# MCU.net
KiCad netlist of a schematic drawn in Altium Designer
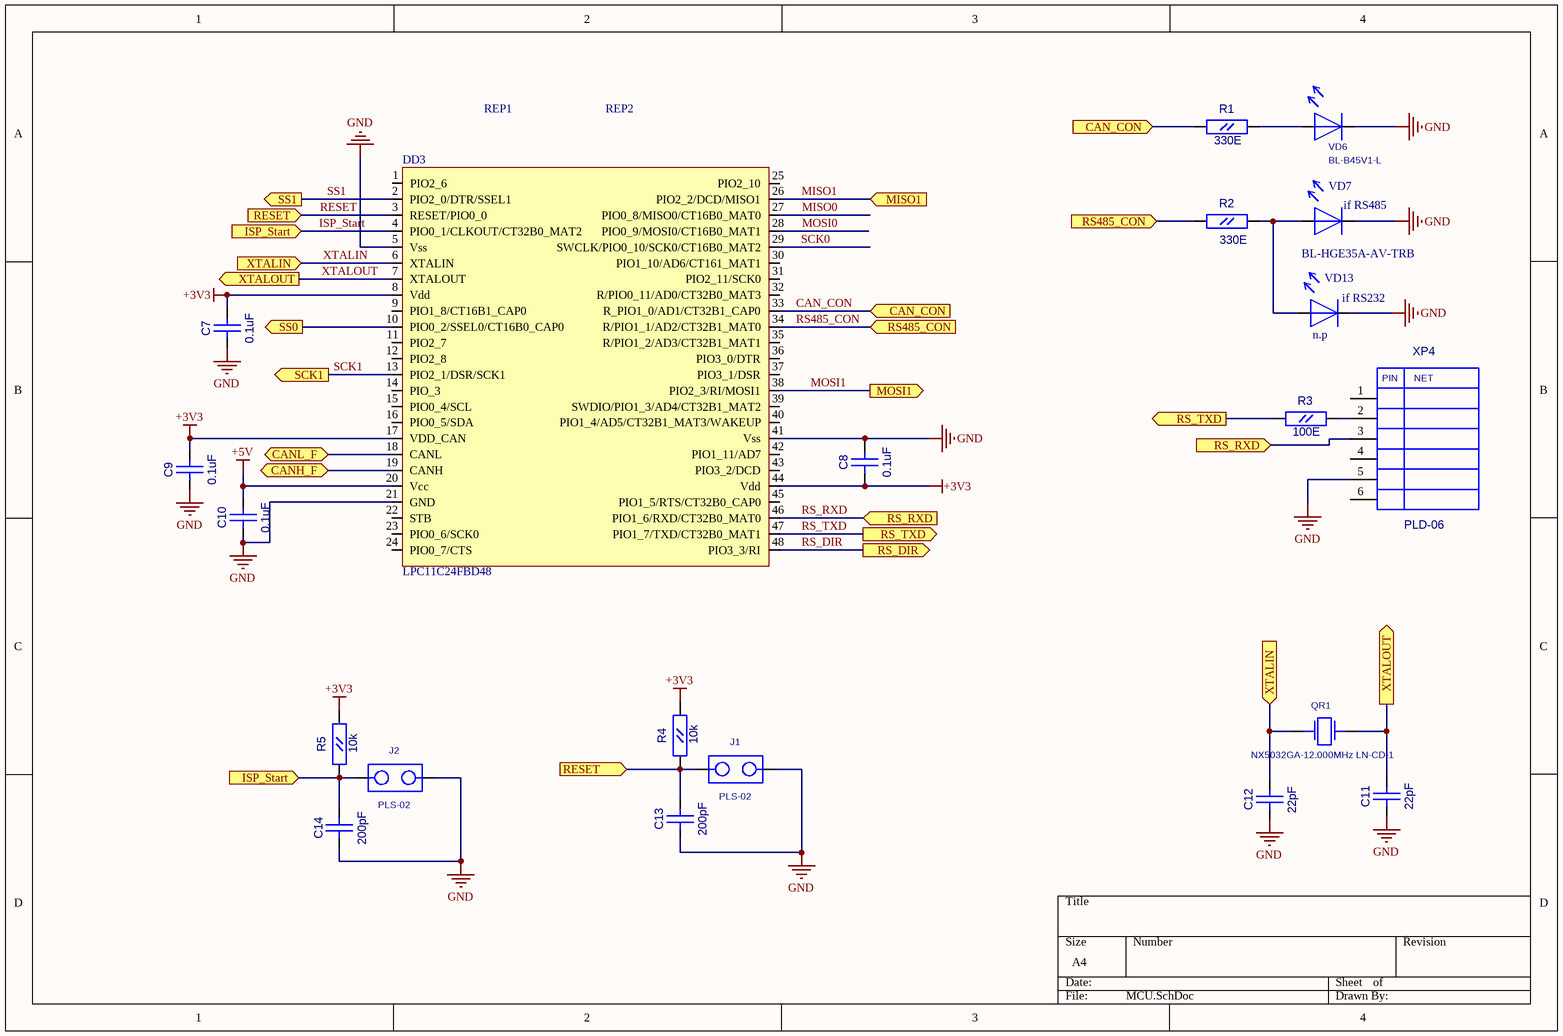
[diagram p0: MCU.SchDoc]

(export (version "E")
  (design (tool "Eeschema 10.0.6"))
  (components
    (comp (ref "C7")
      (value "0.1uF")
      (footprint "CC0603")
      (description "CC0603")
      (libsource (lib "gprs_modem_2") (part "CC0603"))
    )
    (comp (ref "C8")
      (value "0.1uF")
      (footprint "CC0603")
      (description "CC0603")
      (libsource (lib "gprs_modem_2") (part "CC0603"))
    )
    (comp (ref "C9")
      (value "0.1uF")
      (footprint "CC0603")
      (description "CC0603")
      (libsource (lib "gprs_modem_2") (part "CC0603"))
    )
    (comp (ref "C10")
      (value "0.1uF")
      (footprint "CC0603")
      (description "CC0603")
      (libsource (lib "gprs_modem_2") (part "CC0603"))
    )
    (comp (ref "C11")
      (value "22pF")
      (footprint "CC0603")
      (description "CC0603")
      (libsource (lib "gprs_modem_2") (part "CC0603"))
    )
    (comp (ref "C12")
      (value "22pF")
      (footprint "CC0603")
      (description "CC0603")
      (libsource (lib "gprs_modem_2") (part "CC0603"))
    )
    (comp (ref "C13")
      (value "200pF")
      (footprint "CC0603")
      (description "CC0603")
      (libsource (lib "gprs_modem_2") (part "CC0603"))
    )
    (comp (ref "C14")
      (value "200pF")
      (footprint "CC0603")
      (description "CC0603")
      (libsource (lib "gprs_modem_2") (part "CC0603"))
    )
    (comp (ref "DD3")
      (value "LPC11C24FBD48")
      (footprint "LQFP-48")
      (libsource (lib "gprs_modem_2") (part "LPC11C24FBD48"))
    )
    (comp (ref "J1") (value "PLS-02") (footprint "PLS-02") (libsource (lib "gprs_modem_2") (part "PLS-02")))
    (comp (ref "J2") (value "PLS-02") (footprint "PLS-02") (libsource (lib "gprs_modem_2") (part "PLS-02")))
    (comp (ref "QR1")
      (value "NX5032GA-12.000MHz LN-CD-1")
      (footprint "AC5032_2")
      (description "AC5032/2")
      (libsource (lib "gprs_modem_2") (part "AC5032_2"))
    )
    (comp (ref "R1")
      (value "330E")
      (footprint "RC0603")
      (description "RC0603")
      (libsource (lib "gprs_modem_2") (part "RC0603"))
    )
    (comp (ref "R2")
      (value "330E")
      (footprint "RC0603")
      (description "RC0603")
      (libsource (lib "gprs_modem_2") (part "RC0603"))
    )
    (comp (ref "R3")
      (value "100E")
      (footprint "RC0603")
      (description "RC0603")
      (libsource (lib "gprs_modem_2") (part "RC0603"))
    )
    (comp (ref "R4")
      (value "10k")
      (footprint "RC0603")
      (description "RC0603")
      (libsource (lib "gprs_modem_2") (part "RC0603"))
    )
    (comp (ref "R5")
      (value "10k")
      (footprint "RC0603")
      (description "RC0603")
      (libsource (lib "gprs_modem_2") (part "RC0603"))
    )
    (comp (ref "REP1")
      (value "REPER_POINT_1.2")
      (footprint "REPER1.2")
      (description "REPER1.2")
      (libsource (lib "gprs_modem_2") (part "REPER1.2"))
    )
    (comp (ref "REP2")
      (value "REPER_POINT_1.2")
      (footprint "REPER1.2")
      (description "REPER1.2")
      (libsource (lib "gprs_modem_2") (part "REPER1.2"))
    )
    (comp (ref "VD6")
      (value "BL-B45V1-L")
      (footprint "LED3")
      (description "LED_3")
      (libsource (lib "gprs_modem_2") (part "LED_3"))
    )
    (comp (ref "VD7")
      (value "BL-HGE35A-AV-TRB")
      (footprint "LED0805")
      (libsource (lib "gprs_modem_2") (part "LED_0805"))
    )
    (comp (ref "VD13") (value "n.p") (footprint "LED0805") (libsource (lib "") (part "LED_0805_1")))
    (comp (ref "XP4")
      (value "PLD-06")
      (footprint "PIN6")
      (description "PLD06")
      (libsource (lib "gprs_modem") (part "PLD-06"))
    )
  )
  (nets
    (net (code "1") (name "+3V3") (class "Default")
      (node (ref "C7") (pin "2") (pinfunction "B_2") (pintype "passive"))
      (node (ref "C8") (pin "1") (pinfunction "A_1") (pintype "passive"))
      (node (ref "C9") (pin "2") (pinfunction "B_2") (pintype "passive"))
      (node (ref "DD3") (pin "17") (pinfunction "VDD_CAN_17") (pintype "passive"))
      (node (ref "DD3") (pin "44") (pinfunction "Vdd_44") (pintype "passive"))
      (node (ref "DD3") (pin "8") (pinfunction "Vdd_8") (pintype "passive"))
      (node (ref "R4") (pin "2") (pinfunction "B_2") (pintype "passive"))
      (node (ref "R5") (pin "2") (pinfunction "B_2") (pintype "passive"))
    )
    (net (code "2") (name "+5V") (class "Default")
      (node (ref "C10") (pin "2") (pinfunction "B_2") (pintype "passive"))
      (node (ref "DD3") (pin "20") (pinfunction "Vcc_20") (pintype "passive"))
    )
    (net (code "3") (name "/CANH_F") (class "Default")
      (node (ref "DD3") (pin "19") (pinfunction "CANH_19") (pintype "passive"))
    )
    (net (code "4") (name "/CANL_F") (class "Default")
      (node (ref "DD3") (pin "18") (pinfunction "CANL_18") (pintype "passive"))
    )
    (net (code "5") (name "/CAN_CON") (class "Default")
      (node (ref "DD3") (pin "33") (pinfunction "R_PIO1_0/AD1/CT32B1_CAP0_33") (pintype "passive"))
      (node (ref "R1") (pin "1") (pinfunction "A_1") (pintype "passive"))
    )
    (net (code "6") (name "/ISP_Start") (class "Default")
      (node (ref "C14") (pin "2") (pinfunction "B_2") (pintype "passive"))
      (node (ref "DD3") (pin "4") (pinfunction "PIO0_1/CLKOUT/CT32B0_MAT2_4") (pintype "passive"))
      (node (ref "J2") (pin "1") (pintype "passive"))
      (node (ref "R5") (pin "1") (pinfunction "A_1") (pintype "passive"))
    )
    (net (code "7") (name "/MISO0") (class "Default")
      (node (ref "DD3") (pin "27") (pinfunction "PIO0_8/MISO0/CT16B0_MAT0_27") (pintype "passive"))
    )
    (net (code "8") (name "/MISO1") (class "Default")
      (node (ref "DD3") (pin "26") (pinfunction "PIO2_2/DCD/MISO1_26") (pintype "passive"))
    )
    (net (code "9") (name "/MOSI0") (class "Default")
      (node (ref "DD3") (pin "28") (pinfunction "PIO0_9/MOSI0/CT16B0_MAT1_28") (pintype "passive"))
    )
    (net (code "10") (name "/MOSI1") (class "Default")
      (node (ref "DD3") (pin "38") (pinfunction "PIO2_3/RI/MOSI1_38") (pintype "passive"))
    )
    (net (code "11") (name "/RESET") (class "Default")
      (node (ref "C13") (pin "2") (pinfunction "B_2") (pintype "passive"))
      (node (ref "DD3") (pin "3") (pinfunction "RESET/PIO0_0_3") (pintype "passive"))
      (node (ref "J1") (pin "1") (pintype "passive"))
      (node (ref "R4") (pin "1") (pinfunction "A_1") (pintype "passive"))
    )
    (net (code "12") (name "/RS485_CON") (class "Default")
      (node (ref "DD3") (pin "34") (pinfunction "R/PIO1_1/AD2/CT32B1_MAT0_34") (pintype "passive"))
      (node (ref "R2") (pin "1") (pinfunction "A_1") (pintype "passive"))
    )
    (net (code "13") (name "/RS_DIR") (class "Default")
      (node (ref "DD3") (pin "48") (pinfunction "PIO3_3/RI_48") (pintype "passive"))
    )
    (net (code "14") (name "/RS_RXD") (class "Default")
      (node (ref "DD3") (pin "46") (pinfunction "PIO1_6/RXD/CT32B0_MAT0_46") (pintype "passive"))
      (node (ref "XP4") (pin "3") (pinfunction "3_3") (pintype "passive"))
    )
    (net (code "15") (name "/RS_TXD") (class "Default")
      (node (ref "DD3") (pin "47") (pinfunction "PIO1_7/TXD/CT32B0_MAT1_47") (pintype "passive"))
      (node (ref "R3") (pin "1") (pinfunction "A_1") (pintype "passive"))
    )
    (net (code "16") (name "/SCK0") (class "Default")
      (node (ref "DD3") (pin "29") (pinfunction "SWCLK/PIO0_10/SCK0/CT16B0_MAT2_29") (pintype "passive"))
    )
    (net (code "17") (name "/SCK1") (class "Default")
      (node (ref "DD3") (pin "13") (pinfunction "PIO2_1/DSR/SCK1_13") (pintype "passive"))
    )
    (net (code "18") (name "/SS0") (class "Default")
      (node (ref "DD3") (pin "10") (pinfunction "PIO0_2/SSEL0/CT16B0_CAP0_10") (pintype "passive"))
    )
    (net (code "19") (name "/SS1") (class "Default")
      (node (ref "DD3") (pin "2") (pinfunction "PIO2_0/DTR/SSEL1_2") (pintype "passive"))
    )
    (net (code "20") (name "/XTALIN") (class "Default")
      (node (ref "C12") (pin "2") (pinfunction "B_2") (pintype "passive"))
      (node (ref "DD3") (pin "6") (pinfunction "XTALIN_6") (pintype "passive"))
      (node (ref "QR1") (pin "1") (pintype "passive"))
    )
    (net (code "21") (name "/XTALOUT") (class "Default")
      (node (ref "C11") (pin "2") (pinfunction "B_2") (pintype "passive"))
      (node (ref "DD3") (pin "7") (pinfunction "XTALOUT_7") (pintype "passive"))
      (node (ref "QR1") (pin "2") (pintype "passive"))
    )
    (net (code "22") (name "GND") (class "Default")
      (node (ref "C10") (pin "1") (pinfunction "A_1") (pintype "passive"))
      (node (ref "C11") (pin "1") (pinfunction "A_1") (pintype "passive"))
      (node (ref "C12") (pin "1") (pinfunction "A_1") (pintype "passive"))
      (node (ref "C13") (pin "1") (pinfunction "A_1") (pintype "passive"))
      (node (ref "C14") (pin "1") (pinfunction "A_1") (pintype "passive"))
      (node (ref "C7") (pin "1") (pinfunction "A_1") (pintype "passive"))
      (node (ref "C8") (pin "2") (pinfunction "B_2") (pintype "passive"))
      (node (ref "C9") (pin "1") (pinfunction "A_1") (pintype "passive"))
      (node (ref "DD3") (pin "21") (pinfunction "GND_21") (pintype "passive"))
      (node (ref "DD3") (pin "41") (pinfunction "Vss_41") (pintype "passive"))
      (node (ref "DD3") (pin "5") (pinfunction "Vss_5") (pintype "passive"))
      (node (ref "J1") (pin "2") (pintype "passive"))
      (node (ref "J2") (pin "2") (pintype "passive"))
      (node (ref "VD13") (pin "2") (pintype "passive"))
      (node (ref "VD6") (pin "1") (pintype "passive"))
      (node (ref "VD7") (pin "2") (pintype "passive"))
      (node (ref "XP4") (pin "5") (pinfunction "5_5") (pintype "passive"))
    )
    (net (code "23") (name "Net-(R1-B)") (class "Default")
      (node (ref "R1") (pin "2") (pinfunction "B_2") (pintype "passive"))
      (node (ref "VD6") (pin "2") (pintype "passive"))
    )
    (net (code "24") (name "Net-(R2-B)") (class "Default")
      (node (ref "R2") (pin "2") (pinfunction "B_2") (pintype "passive"))
      (node (ref "VD13") (pin "1") (pintype "passive"))
      (node (ref "VD7") (pin "1") (pintype "passive"))
    )
    (net (code "25") (name "Net-(R3-B)") (class "Default")
      (node (ref "R3") (pin "2") (pinfunction "B_2") (pintype "passive"))
      (node (ref "XP4") (pin "2") (pinfunction "2_2") (pintype "passive"))
    )
    (net (code "26") (name "unconnected-(DD3-PIO0_4{slash}SCL-Pad15)") (class "Default")
      (node (ref "DD3") (pin "15") (pinfunction "PIO0_4/SCL_15") (pintype "passive"))
    )
    (net (code "27") (name "unconnected-(DD3-PIO0_5{slash}SDA-Pad16)") (class "Default")
      (node (ref "DD3") (pin "16") (pinfunction "PIO0_5/SDA_16") (pintype "passive"))
    )
    (net (code "28") (name "unconnected-(DD3-PIO0_6{slash}SCK0-Pad23)") (class "Default")
      (node (ref "DD3") (pin "23") (pinfunction "PIO0_6/SCK0_23") (pintype "passive"))
    )
    (net (code "29") (name "unconnected-(DD3-PIO0_7{slash}CTS-Pad24)") (class "Default")
      (node (ref "DD3") (pin "24") (pinfunction "PIO0_7/CTS_24") (pintype "passive"))
    )
    (net (code "30") (name "unconnected-(DD3-PIO1_4{slash}AD5{slash}CT32B1_MAT3{slash}WAKEUP-Pad40)") (class "Default")
      (node (ref "DD3") (pin "40") (pinfunction "PIO1_4/AD5/CT32B1_MAT3/WAKEUP_40") (pintype "passive"))
    )
    (net (code "31") (name "unconnected-(DD3-PIO1_5{slash}RTS{slash}CT32B0_CAP0-Pad45)") (class "Default")
      (node (ref "DD3") (pin "45") (pinfunction "PIO1_5/RTS/CT32B0_CAP0_45") (pintype "passive"))
    )
    (net (code "32") (name "unconnected-(DD3-PIO1_8{slash}CT16B1_CAP0-Pad9)") (class "Default")
      (node (ref "DD3") (pin "9") (pinfunction "PIO1_8/CT16B1_CAP0_9") (pintype "passive"))
    )
    (net (code "33") (name "unconnected-(DD3-PIO1_10{slash}AD6{slash}CT161_MAT1-Pad30)") (class "Default")
      (node (ref "DD3") (pin "30") (pinfunction "PIO1_10/AD6/CT161_MAT1_30") (pintype "passive"))
    )
    (net (code "34") (name "unconnected-(DD3-PIO1_11{slash}AD7-Pad42)") (class "Default")
      (node (ref "DD3") (pin "42") (pinfunction "PIO1_11/AD7_42") (pintype "passive"))
    )
    (net (code "35") (name "unconnected-(DD3-PIO2_6-Pad1)") (class "Default")
      (node (ref "DD3") (pin "1") (pinfunction "PIO2_6_1") (pintype "passive"))
    )
    (net (code "36") (name "unconnected-(DD3-PIO2_7-Pad11)") (class "Default")
      (node (ref "DD3") (pin "11") (pinfunction "PIO2_7_11") (pintype "passive"))
    )
    (net (code "37") (name "unconnected-(DD3-PIO2_8-Pad12)") (class "Default")
      (node (ref "DD3") (pin "12") (pinfunction "PIO2_8_12") (pintype "passive"))
    )
    (net (code "38") (name "unconnected-(DD3-PIO2_10-Pad25)") (class "Default")
      (node (ref "DD3") (pin "25") (pinfunction "PIO2_10_25") (pintype "passive"))
    )
    (net (code "39") (name "unconnected-(DD3-PIO2_11{slash}SCK0-Pad31)") (class "Default")
      (node (ref "DD3") (pin "31") (pinfunction "PIO2_11/SCK0_31") (pintype "passive"))
    )
    (net (code "40") (name "unconnected-(DD3-PIO3_0{slash}DTR-Pad36)") (class "Default")
      (node (ref "DD3") (pin "36") (pinfunction "PIO3_0/DTR_36") (pintype "passive"))
    )
    (net (code "41") (name "unconnected-(DD3-PIO3_1{slash}DSR-Pad37)") (class "Default")
      (node (ref "DD3") (pin "37") (pinfunction "PIO3_1/DSR_37") (pintype "passive"))
    )
    (net (code "42") (name "unconnected-(DD3-PIO3_2{slash}DCD-Pad43)") (class "Default")
      (node (ref "DD3") (pin "43") (pinfunction "PIO3_2/DCD_43") (pintype "passive"))
    )
    (net (code "43") (name "unconnected-(DD3-PIO_3-Pad14)") (class "Default")
      (node (ref "DD3") (pin "14") (pinfunction "PIO_3_14") (pintype "passive"))
    )
    (net (code "44") (name "unconnected-(DD3-R{slash}PIO0_11{slash}AD0{slash}CT32B0_MAT3-Pad32)") (class "Default")
      (node (ref "DD3") (pin "32") (pinfunction "R/PIO0_11/AD0/CT32B0_MAT3_32") (pintype "passive"))
    )
    (net (code "45") (name "unconnected-(DD3-R{slash}PIO1_2{slash}AD3{slash}CT32B1_MAT1-Pad35)") (class "Default")
      (node (ref "DD3") (pin "35") (pinfunction "R/PIO1_2/AD3/CT32B1_MAT1_35") (pintype "passive"))
    )
    (net (code "46") (name "unconnected-(DD3-STB-Pad22)") (class "Default")
      (node (ref "DD3") (pin "22") (pinfunction "STB_22") (pintype "passive"))
    )
    (net (code "47") (name "unconnected-(DD3-SWDIO{slash}PIO1_3{slash}AD4{slash}CT32B1_MAT2-Pad39)") (class "Default")
      (node (ref "DD3") (pin "39") (pinfunction "SWDIO/PIO1_3/AD4/CT32B1_MAT2_39") (pintype "passive"))
    )
    (net (code "48") (name "unconnected-(REP1-Pad1)") (class "Default")
      (node (ref "REP1") (pin "1") (pintype "passive"))
    )
    (net (code "49") (name "unconnected-(REP2-Pad1)") (class "Default")
      (node (ref "REP2") (pin "1") (pintype "passive"))
    )
    (net (code "50") (name "unconnected-(XP4-Pad1)") (class "Default")
      (node (ref "XP4") (pin "1") (pinfunction "1_1") (pintype "passive"))
    )
    (net (code "51") (name "unconnected-(XP4-Pad4)") (class "Default")
      (node (ref "XP4") (pin "4") (pinfunction "4_4") (pintype "passive"))
    )
    (net (code "52") (name "unconnected-(XP4-Pad6)") (class "Default")
      (node (ref "XP4") (pin "6") (pinfunction "6_6") (pintype "passive"))
    )
  )
)
